# MPLAB-ICD-Inline.net
KiCad netlist of a schematic drawn in Altium Designer
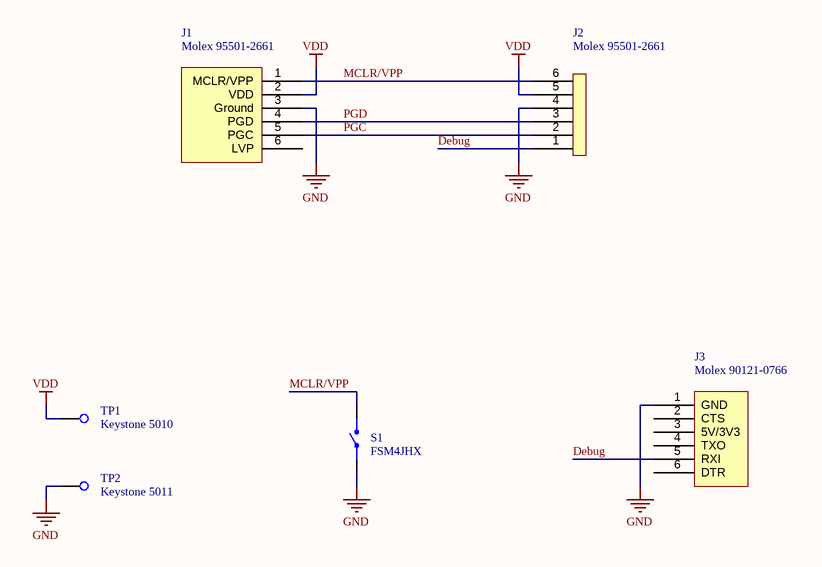
[diagram p0: MPLAB-ICD-Inline.SchDoc]

(export (version "E")
  (design (tool "Eeschema 10.0.6"))
  (components
    (comp (ref "J1")
      (value "Molex 95501-2661")
      (footprint "Molex 95501-2661")
      (libsource (lib "x-io") (part "MPLAB ICSP"))
    )
    (comp (ref "J2")
      (value "Molex 95501-2661")
      (footprint "Molex 95501-2661")
      (libsource (lib "x-io") (part "Molex 95501-2661"))
    )
    (comp (ref "J3")
      (value "Molex 90121-0766")
      (footprint "Molex 90121-0766 with FTDI Breakout")
      (libsource (lib "x-io") (part "FTDI Breakout"))
    )
    (comp (ref "S1") (value "FSM4JHX") (footprint "FSM4JHX") (libsource (lib "x-io") (part "Switch")))
    (comp (ref "TP1")
      (value "Keystone 5010")
      (footprint "Keystone 5010")
      (libsource (lib "x-io") (part "Test Point"))
    )
    (comp (ref "TP2")
      (value "Keystone 5011")
      (footprint "Keystone 5011")
      (libsource (lib "x-io") (part "Test Point"))
    )
  )
  (nets
    (net (code "1") (name "/Debug") (class "Default")
      (node (ref "J2") (pin "1") (pinfunction "1_1") (pintype "passive"))
      (node (ref "J3") (pin "5") (pinfunction "RXI_5") (pintype "passive"))
    )
    (net (code "2") (name "/MCLR{slash}VPP") (class "Default")
      (node (ref "J1") (pin "1") (pinfunction "MCLR/VPP_1") (pintype "passive"))
      (node (ref "J2") (pin "6") (pinfunction "6_6") (pintype "passive"))
      (node (ref "S1") (pin "2") (pinfunction "2_2") (pintype "passive"))
    )
    (net (code "3") (name "/PGC") (class "Default")
      (node (ref "J1") (pin "5") (pinfunction "PGC_5") (pintype "passive"))
      (node (ref "J2") (pin "2") (pinfunction "2_2") (pintype "passive"))
    )
    (net (code "4") (name "/PGD") (class "Default")
      (node (ref "J1") (pin "4") (pinfunction "PGD_4") (pintype "passive"))
      (node (ref "J2") (pin "3") (pinfunction "3_3") (pintype "passive"))
    )
    (net (code "5") (name "GND") (class "Default")
      (node (ref "J1") (pin "3") (pinfunction "Ground_3") (pintype "passive"))
      (node (ref "J2") (pin "4") (pinfunction "4_4") (pintype "passive"))
      (node (ref "J3") (pin "1") (pinfunction "GND_1") (pintype "passive"))
      (node (ref "S1") (pin "1") (pinfunction "1_1") (pintype "passive"))
      (node (ref "TP2") (pin "1") (pinfunction "1_1") (pintype "passive"))
    )
    (net (code "6") (name "VDD") (class "Default")
      (node (ref "J1") (pin "2") (pinfunction "VDD_2") (pintype "passive"))
      (node (ref "J2") (pin "5") (pinfunction "5_5") (pintype "passive"))
      (node (ref "TP1") (pin "1") (pinfunction "1_1") (pintype "passive"))
    )
    (net (code "7") (name "unconnected-(J1-LVP-Pad6)") (class "Default")
      (node (ref "J1") (pin "6") (pinfunction "LVP_6") (pintype "passive"))
    )
    (net (code "8") (name "unconnected-(J3-5V{slash}3V3-Pad3)") (class "Default")
      (node (ref "J3") (pin "3") (pinfunction "5V/3V3_3") (pintype "passive"))
    )
    (net (code "9") (name "unconnected-(J3-CTS-Pad2)") (class "Default")
      (node (ref "J3") (pin "2") (pinfunction "CTS_2") (pintype "passive"))
    )
    (net (code "10") (name "unconnected-(J3-DTR-Pad6)") (class "Default")
      (node (ref "J3") (pin "6") (pinfunction "DTR_6") (pintype "passive"))
    )
    (net (code "11") (name "unconnected-(J3-TXO-Pad4)") (class "Default")
      (node (ref "J3") (pin "4") (pinfunction "TXO_4") (pintype "passive"))
    )
  )
)
